# 1-TX510_KIT.net
KiCad netlist of a schematic drawn in Altium Designer
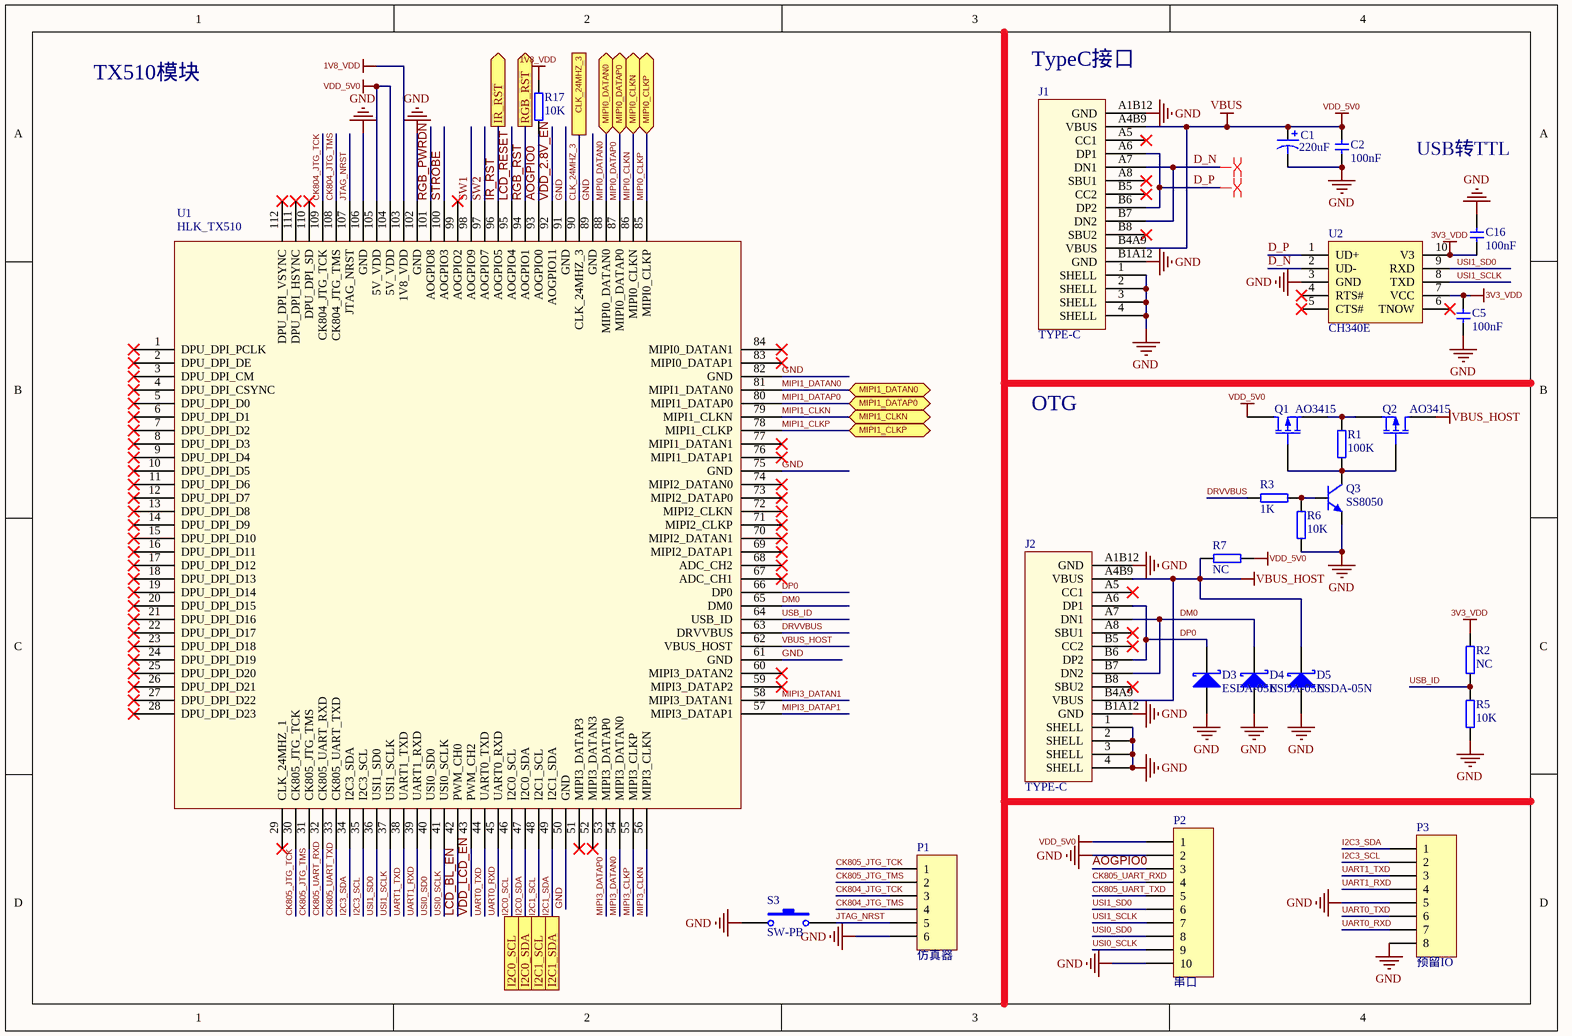
[diagram p0: 1-TX510_KIT.SchDoc]

(export (version "E")
  (design (tool "Eeschema 10.0.6"))
  (components
    (comp (ref "C1")
      (value "220uF")
      (footprint "SMD,6.3x7.7mm")
      (description "Polarized Capacitor (Radial)")
      (fields (field (name "Comment") "Cap Pol1") (field (name "PUBLISHER") "Altium Limited"))
      (libsource (lib "Miscellaneous Devices") (part "Cap Pol1"))
    )
    (comp (ref "C2")
      (value "100nF")
      (footprint "C0402")
      (description "C?")
      (libsource (lib "HNCY_SCH_Lib") (part "CAP1"))
    )
    (comp (ref "C5")
      (value "100nF")
      (footprint "C0402")
      (description "C?")
      (libsource (lib "HNCY_SCH_Lib") (part "CAP1"))
    )
    (comp (ref "C16")
      (value "100nF")
      (footprint "C0402")
      (description "C?")
      (libsource (lib "HNCY_SCH_Lib") (part "CAP1"))
    )
    (comp (ref "D3")
      (value "ESDA-05N")
      (footprint "R0402")
      (description "Silicon AF Schottky Diode for High-Speed Switching")
      (fields (field (name "PUBLISHER") "Altium Limited"))
      (libsource (lib "Miscellaneous Devices") (part "Diode BAS70"))
    )
    (comp (ref "D4")
      (value "ESDA-05N")
      (footprint "R0402")
      (description "Silicon AF Schottky Diode for High-Speed Switching")
      (fields (field (name "PUBLISHER") "Altium Limited"))
      (libsource (lib "Miscellaneous Devices") (part "Diode BAS70"))
    )
    (comp (ref "D5")
      (value "ESDA-05N")
      (footprint "R0402")
      (description "Silicon AF Schottky Diode for High-Speed Switching")
      (fields (field (name "PUBLISHER") "Altium Limited"))
      (libsource (lib "Miscellaneous Devices") (part "Diode BAS70"))
    )
    (comp (ref "J1") (value "TYPE-C") (footprint "TYPE-C16PIN") (libsource (lib "*") (part "TYPE-C16PIN")))
    (comp (ref "J2") (value "TYPE-C") (footprint "TYPE-C16PIN") (libsource (lib "*") (part "TYPE-C16PIN")))
    (comp (ref "P1")
      (value "仿真器")
      (footprint "HDR1X6")
      (description "Header, 6-Pin")
      (fields (field (name "PUBLISHER") "Altium Limited"))
      (libsource (lib "Miscellaneous Connectors") (part "Header 6"))
    )
    (comp (ref "P2")
      (value "串口")
      (footprint "HDR1X10")
      (description "Header, 10-Pin")
      (fields (field (name "PUBLISHER") "Altium Limited"))
      (libsource (lib "Miscellaneous Connectors") (part "Header 10"))
    )
    (comp (ref "P3")
      (value "预留IO")
      (footprint "HDR1X8")
      (description "Header, 8-Pin")
      (fields (field (name "PUBLISHER") "Altium Limited"))
      (libsource (lib "Miscellaneous Connectors") (part "Header 8"))
    )
    (comp (ref "Q1") (value "AO3415") (footprint "SOT-23") (libsource (lib "*") (part "AO3415")))
    (comp (ref "Q2") (value "AO3415") (footprint "SOT-23") (libsource (lib "*") (part "AO3415")))
    (comp (ref "Q3")
      (value "SS8050")
      (footprint "SOT23-BEC")
      (description "贴片三极管")
      (libsource (lib "HNCY_SCH_Lib") (part "NPN"))
    )
    (comp (ref "R1")
      (value "100K")
      (footprint "R0402")
      (description "R?")
      (libsource (lib "HNCY_SCH_Lib") (part "RES1"))
    )
    (comp (ref "R2")
      (value "NC")
      (footprint "R0402")
      (description "R?")
      (libsource (lib "HNCY_SCH_Lib") (part "RES1"))
    )
    (comp (ref "R3")
      (value "1K")
      (footprint "R0402")
      (description "R?")
      (libsource (lib "HNCY_SCH_Lib") (part "RES1"))
    )
    (comp (ref "R5")
      (value "10K")
      (footprint "R0402")
      (description "R?")
      (libsource (lib "HNCY_SCH_Lib") (part "RES1"))
    )
    (comp (ref "R6")
      (value "10K")
      (footprint "R0402")
      (description "R?")
      (libsource (lib "HNCY_SCH_Lib") (part "RES1"))
    )
    (comp (ref "R7")
      (value "NC")
      (footprint "RES_0603")
      (description "R?")
      (libsource (lib "HNCY_SCH_Lib") (part "RES1"))
    )
    (comp (ref "R17")
      (value "10K")
      (footprint "R0402")
      (description "R?")
      (libsource (lib "HNCY_SCH_Lib") (part "RES1"))
    )
    (comp (ref "S3")
      (value "SW-PB")
      (footprint "轻触开关4.5x4.5")
      (description "Switch")
      (fields (field (name "PUBLISHER") "Altium Limited"))
      (libsource (lib "Miscellaneous Devices") (part "SW-PB"))
    )
    (comp (ref "U1")
      (value "HLK_TX510")
      (footprint "HLK_TX510 _KIT")
      (libsource (lib "MY SCHLIB") (part "HLK_TX510"))
    )
    (comp (ref "U2") (value "CH340E") (footprint "MSOP-10") (libsource (lib "MY SCHLIB") (part "CH340E")))
  )
  (nets
    (net (code "1") (name "/AOGPIO0") (class "Default")
      (node (ref "P2") (pin "3") (pinfunction "3_3") (pintype "passive"))
      (node (ref "R17") (pin "1") (pinfunction "1_1") (pintype "passive"))
      (node (ref "U1") (pin "93") (pinfunction "AOGPIO0_93") (pintype "passive"))
    )
    (net (code "2") (name "/CK804_JTG_TCK") (class "Default")
      (node (ref "P1") (pin "3") (pinfunction "3_3") (pintype "passive"))
      (node (ref "U1") (pin "109") (pinfunction "CK804_JTG_TCK_109") (pintype "passive"))
    )
    (net (code "3") (name "/CK804_JTG_TMS") (class "Default")
      (node (ref "P1") (pin "4") (pinfunction "4_4") (pintype "passive"))
      (node (ref "U1") (pin "108") (pinfunction "CK804_JTG_TMS_108") (pintype "passive"))
    )
    (net (code "4") (name "/CK805_JTG_TCK") (class "Default")
      (node (ref "P1") (pin "1") (pinfunction "1_1") (pintype "passive"))
      (node (ref "U1") (pin "30") (pinfunction "CK805_JTG_TCK_30") (pintype "passive"))
    )
    (net (code "5") (name "/CK805_JTG_TMS") (class "Default")
      (node (ref "P1") (pin "2") (pinfunction "2_2") (pintype "passive"))
      (node (ref "U1") (pin "31") (pinfunction "CK805_JTG_TMS_31") (pintype "passive"))
    )
    (net (code "6") (name "/CK805_UART_RXD") (class "Default")
      (node (ref "P2") (pin "4") (pinfunction "4_4") (pintype "passive"))
      (node (ref "U1") (pin "32") (pinfunction "CK805_UART_RXD_32") (pintype "passive"))
    )
    (net (code "7") (name "/CK805_UART_TXD") (class "Default")
      (node (ref "P2") (pin "5") (pinfunction "5_5") (pintype "passive"))
      (node (ref "U1") (pin "33") (pinfunction "CK805_UART_TXD_33") (pintype "passive"))
    )
    (net (code "8") (name "/CLK_24MHZ_3") (class "Default")
      (node (ref "U1") (pin "90") (pinfunction "CLK_24MHZ_3_90") (pintype "passive"))
    )
    (net (code "9") (name "/DM0") (class "Default")
      (node (ref "D4") (pin "2") (pinfunction "K_2") (pintype "passive"))
      (node (ref "J2") (pin "A7") (pinfunction "DN1_A7") (pintype "passive"))
      (node (ref "J2") (pin "B7") (pinfunction "DN2_B7") (pintype "passive"))
      (node (ref "U1") (pin "65") (pinfunction "DM0_65") (pintype "passive"))
    )
    (net (code "10") (name "/DP0") (class "Default")
      (node (ref "D3") (pin "2") (pinfunction "K_2") (pintype "passive"))
      (node (ref "J2") (pin "A6") (pinfunction "DP1_A6") (pintype "passive"))
      (node (ref "J2") (pin "B6") (pinfunction "DP2_B6") (pintype "passive"))
      (node (ref "U1") (pin "66") (pinfunction "DP0_66") (pintype "passive"))
    )
    (net (code "11") (name "/DRVVBUS") (class "Default")
      (node (ref "R3") (pin "2") (pinfunction "2_2") (pintype "passive"))
      (node (ref "U1") (pin "63") (pinfunction "DRVVBUS_63") (pintype "passive"))
    )
    (net (code "12") (name "/D_N") (class "Default")
      (node (ref "J1") (pin "A7") (pinfunction "DN1_A7") (pintype "passive"))
      (node (ref "J1") (pin "B7") (pinfunction "DN2_B7") (pintype "passive"))
      (node (ref "U2") (pin "2") (pinfunction "UD-_2") (pintype "passive"))
    )
    (net (code "13") (name "/D_P") (class "Default")
      (node (ref "J1") (pin "A6") (pinfunction "DP1_A6") (pintype "passive"))
      (node (ref "J1") (pin "B6") (pinfunction "DP2_B6") (pintype "passive"))
      (node (ref "U2") (pin "1") (pinfunction "UD+_1") (pintype "passive"))
    )
    (net (code "14") (name "/I2C0_SCL") (class "Default")
      (node (ref "U1") (pin "46") (pinfunction "I2C0_SCL_46") (pintype "passive"))
    )
    (net (code "15") (name "/I2C0_SDA") (class "Default")
      (node (ref "U1") (pin "47") (pinfunction "I2C0_SDA_47") (pintype "passive"))
    )
    (net (code "16") (name "/I2C1_SCL") (class "Default")
      (node (ref "U1") (pin "48") (pinfunction "I2C1_SCL_48") (pintype "passive"))
    )
    (net (code "17") (name "/I2C1_SDA") (class "Default")
      (node (ref "U1") (pin "49") (pinfunction "I2C1_SDA_49") (pintype "passive"))
    )
    (net (code "18") (name "/I2C3_SCL") (class "Default")
      (node (ref "P3") (pin "2") (pinfunction "2_2") (pintype "passive"))
      (node (ref "U1") (pin "35") (pinfunction "I2C3_SCL_35") (pintype "passive"))
    )
    (net (code "19") (name "/I2C3_SDA") (class "Default")
      (node (ref "P3") (pin "1") (pinfunction "1_1") (pintype "passive"))
      (node (ref "U1") (pin "34") (pinfunction "I2C3_SDA_34") (pintype "passive"))
    )
    (net (code "20") (name "/IR_RST") (class "Default")
      (node (ref "U1") (pin "96") (pinfunction "AOGPIO5_96") (pintype "passive"))
    )
    (net (code "21") (name "/JTAG_NRST") (class "Default")
      (node (ref "P1") (pin "5") (pinfunction "5_5") (pintype "passive"))
      (node (ref "S3") (pin "2") (pinfunction "2_2") (pintype "passive"))
      (node (ref "U1") (pin "107") (pinfunction "JTAG_NRST_107") (pintype "passive"))
    )
    (net (code "22") (name "/LCD_BL_EN") (class "Default")
      (node (ref "U1") (pin "42") (pinfunction "PWM_CH0_42") (pintype "passive"))
    )
    (net (code "23") (name "/LCD_RESET") (class "Default")
      (node (ref "U1") (pin "95") (pinfunction "AOGPIO4_95") (pintype "passive"))
    )
    (net (code "24") (name "/MIPI0_CLKN") (class "Default")
      (node (ref "U1") (pin "86") (pinfunction "MIPI0_CLKN_86") (pintype "passive"))
    )
    (net (code "25") (name "/MIPI0_CLKP") (class "Default")
      (node (ref "U1") (pin "85") (pinfunction "MIPI0_CLKP_85") (pintype "passive"))
    )
    (net (code "26") (name "/MIPI0_DATAN0") (class "Default")
      (node (ref "U1") (pin "88") (pinfunction "MIPI0_DATAN0_88") (pintype "passive"))
    )
    (net (code "27") (name "/MIPI0_DATAP0") (class "Default")
      (node (ref "U1") (pin "87") (pinfunction "MIPI0_DATAP0_87") (pintype "passive"))
    )
    (net (code "28") (name "/MIPI1_CLKN") (class "Default")
      (node (ref "U1") (pin "79") (pinfunction "MIPI1_CLKN_79") (pintype "passive"))
    )
    (net (code "29") (name "/MIPI1_CLKP") (class "Default")
      (node (ref "U1") (pin "78") (pinfunction "MIPI1_CLKP_78") (pintype "passive"))
    )
    (net (code "30") (name "/MIPI1_DATAN0") (class "Default")
      (node (ref "U1") (pin "81") (pinfunction "MIPI1_DATAN0_81") (pintype "passive"))
    )
    (net (code "31") (name "/MIPI1_DATAP0") (class "Default")
      (node (ref "U1") (pin "80") (pinfunction "MIPI1_DATAP0_80") (pintype "passive"))
    )
    (net (code "32") (name "/MIPI3_CLKN") (class "Default")
      (node (ref "U1") (pin "56") (pinfunction "MIPI3_CLKN_56") (pintype "passive"))
    )
    (net (code "33") (name "/MIPI3_CLKP") (class "Default")
      (node (ref "U1") (pin "55") (pinfunction "MIPI3_CLKP_55") (pintype "passive"))
    )
    (net (code "34") (name "/MIPI3_DATAN0") (class "Default")
      (node (ref "U1") (pin "54") (pinfunction "MIPI3_DATAN0_54") (pintype "passive"))
    )
    (net (code "35") (name "/MIPI3_DATAN1") (class "Default")
      (node (ref "U1") (pin "58") (pinfunction "MIPI3_DATAN1_58") (pintype "passive"))
    )
    (net (code "36") (name "/MIPI3_DATAP0") (class "Default")
      (node (ref "U1") (pin "53") (pinfunction "MIPI3_DATAP0_53") (pintype "passive"))
    )
    (net (code "37") (name "/MIPI3_DATAP1") (class "Default")
      (node (ref "U1") (pin "57") (pinfunction "MIPI3_DATAP1_57") (pintype "passive"))
    )
    (net (code "38") (name "/RGB_PWRDN") (class "Default")
      (node (ref "U1") (pin "101") (pinfunction "AOGPIO8_101") (pintype "passive"))
    )
    (net (code "39") (name "/RGB_RST") (class "Default")
      (node (ref "U1") (pin "94") (pinfunction "AOGPIO1_94") (pintype "passive"))
    )
    (net (code "40") (name "/STROBE") (class "Default")
      (node (ref "U1") (pin "100") (pinfunction "AOGPIO3_100") (pintype "passive"))
    )
    (net (code "41") (name "/SW1") (class "Default")
      (node (ref "U1") (pin "98") (pinfunction "AOGPIO9_98") (pintype "passive"))
    )
    (net (code "42") (name "/SW2") (class "Default")
      (node (ref "U1") (pin "97") (pinfunction "AOGPIO7_97") (pintype "passive"))
    )
    (net (code "43") (name "/UART0_RXD") (class "Default")
      (node (ref "P3") (pin "7") (pinfunction "7_7") (pintype "passive"))
      (node (ref "U1") (pin "45") (pinfunction "UART0_RXD_45") (pintype "passive"))
    )
    (net (code "44") (name "/UART0_TXD") (class "Default")
      (node (ref "P3") (pin "6") (pinfunction "6_6") (pintype "passive"))
      (node (ref "U1") (pin "44") (pinfunction "UART0_TXD_44") (pintype "passive"))
    )
    (net (code "45") (name "/UART1_RXD") (class "Default")
      (node (ref "P3") (pin "4") (pinfunction "4_4") (pintype "passive"))
      (node (ref "U1") (pin "39") (pinfunction "UART1_RXD_39") (pintype "passive"))
    )
    (net (code "46") (name "/UART1_TXD") (class "Default")
      (node (ref "P3") (pin "3") (pinfunction "3_3") (pintype "passive"))
      (node (ref "U1") (pin "38") (pinfunction "UART1_TXD_38") (pintype "passive"))
    )
    (net (code "47") (name "/USB_ID") (class "Default")
      (node (ref "R2") (pin "1") (pinfunction "1_1") (pintype "passive"))
      (node (ref "R5") (pin "2") (pinfunction "2_2") (pintype "passive"))
      (node (ref "U1") (pin "64") (pinfunction "USB_ID_64") (pintype "passive"))
    )
    (net (code "48") (name "/USI0_SCLK") (class "Default")
      (node (ref "P2") (pin "9") (pinfunction "9_9") (pintype "passive"))
      (node (ref "U1") (pin "41") (pinfunction "USI0_SCLK_41") (pintype "passive"))
    )
    (net (code "49") (name "/USI0_SD0") (class "Default")
      (node (ref "P2") (pin "8") (pinfunction "8_8") (pintype "passive"))
      (node (ref "U1") (pin "40") (pinfunction "USI0_SD0_40") (pintype "passive"))
    )
    (net (code "50") (name "/USI1_SCLK") (class "Default")
      (node (ref "P2") (pin "7") (pinfunction "7_7") (pintype "passive"))
      (node (ref "U1") (pin "37") (pinfunction "USI1_SCLK_37") (pintype "passive"))
      (node (ref "U2") (pin "8") (pinfunction "TXD_8") (pintype "passive"))
    )
    (net (code "51") (name "/USI1_SD0") (class "Default")
      (node (ref "P2") (pin "6") (pinfunction "6_6") (pintype "passive"))
      (node (ref "U1") (pin "36") (pinfunction "USI1_SD0_36") (pintype "passive"))
      (node (ref "U2") (pin "9") (pinfunction "RXD_9") (pintype "passive"))
    )
    (net (code "52") (name "/VDD_2.8V_EN") (class "Default")
      (node (ref "U1") (pin "92") (pinfunction "AOGPIO11_92") (pintype "passive"))
    )
    (net (code "53") (name "/VDD_LCD_EN") (class "Default")
      (node (ref "U1") (pin "43") (pinfunction "PWM_CH2_43") (pintype "passive"))
    )
    (net (code "54") (name "1V8_VDD") (class "Default")
      (node (ref "R17") (pin "2") (pinfunction "2_2") (pintype "passive"))
      (node (ref "U1") (pin "103") (pinfunction "1V8_VDD_103") (pintype "passive"))
    )
    (net (code "55") (name "3V3_VDD") (class "Default")
      (node (ref "C16") (pin "1") (pintype "passive"))
      (node (ref "C5") (pin "2") (pintype "passive"))
      (node (ref "R2") (pin "2") (pinfunction "2_2") (pintype "passive"))
      (node (ref "U2") (pin "10") (pinfunction "V3_10") (pintype "passive"))
      (node (ref "U2") (pin "7") (pinfunction "VCC_7") (pintype "passive"))
    )
    (net (code "56") (name "GND") (class "Default")
      (node (ref "C1") (pin "2") (pinfunction "2_2") (pintype "passive"))
      (node (ref "C16") (pin "2") (pintype "passive"))
      (node (ref "C2") (pin "1") (pintype "passive"))
      (node (ref "C5") (pin "1") (pintype "passive"))
      (node (ref "D3") (pin "1") (pinfunction "A_1") (pintype "passive"))
      (node (ref "D4") (pin "1") (pinfunction "A_1") (pintype "passive"))
      (node (ref "D5") (pin "1") (pinfunction "A_1") (pintype "passive"))
      (node (ref "J1") (pin "1") (pinfunction "SHELL_1") (pintype "passive"))
      (node (ref "J1") (pin "2") (pinfunction "SHELL_2") (pintype "passive"))
      (node (ref "J1") (pin "3") (pinfunction "SHELL_3") (pintype "passive"))
      (node (ref "J1") (pin "4") (pinfunction "SHELL_4") (pintype "passive"))
      (node (ref "J1") (pin "A1B12") (pinfunction "GND_A1B12") (pintype "passive"))
      (node (ref "J1") (pin "B1A12") (pinfunction "GND_B1A12") (pintype "passive"))
      (node (ref "J2") (pin "1") (pinfunction "SHELL_1") (pintype "passive"))
      (node (ref "J2") (pin "2") (pinfunction "SHELL_2") (pintype "passive"))
      (node (ref "J2") (pin "3") (pinfunction "SHELL_3") (pintype "passive"))
      (node (ref "J2") (pin "4") (pinfunction "SHELL_4") (pintype "passive"))
      (node (ref "J2") (pin "A1B12") (pinfunction "GND_A1B12") (pintype "passive"))
      (node (ref "J2") (pin "B1A12") (pinfunction "GND_B1A12") (pintype "passive"))
      (node (ref "P1") (pin "6") (pinfunction "6_6") (pintype "passive"))
      (node (ref "P2") (pin "10") (pinfunction "10_10") (pintype "passive"))
      (node (ref "P2") (pin "2") (pinfunction "2_2") (pintype "passive"))
      (node (ref "P3") (pin "5") (pinfunction "5_5") (pintype "passive"))
      (node (ref "P3") (pin "8") (pinfunction "8_8") (pintype "passive"))
      (node (ref "Q3") (pin "E") (pinfunction "E_E") (pintype "passive"))
      (node (ref "R5") (pin "1") (pinfunction "1_1") (pintype "passive"))
      (node (ref "R6") (pin "1") (pinfunction "1_1") (pintype "passive"))
      (node (ref "S3") (pin "1") (pinfunction "1_1") (pintype "passive"))
      (node (ref "U1") (pin "102") (pinfunction "GND_102") (pintype "passive"))
      (node (ref "U1") (pin "106") (pinfunction "GND_106") (pintype "passive"))
      (node (ref "U1") (pin "50") (pinfunction "GND_50") (pintype "passive"))
      (node (ref "U1") (pin "61") (pinfunction "GND_61") (pintype "passive"))
      (node (ref "U1") (pin "75") (pinfunction "GND_75") (pintype "passive"))
      (node (ref "U1") (pin "82") (pinfunction "GND_82") (pintype "passive"))
      (node (ref "U1") (pin "89") (pinfunction "GND_89") (pintype "passive"))
      (node (ref "U1") (pin "91") (pinfunction "GND_91") (pintype "passive"))
      (node (ref "U2") (pin "3") (pinfunction "GND_3") (pintype "passive"))
    )
    (net (code "57") (name "Net-(Q1-G)") (class "Default")
      (node (ref "Q1") (pin "1") (pinfunction "G_1") (pintype "passive"))
      (node (ref "Q2") (pin "1") (pinfunction "G_1") (pintype "passive"))
      (node (ref "Q3") (pin "C") (pinfunction "C_C") (pintype "passive"))
      (node (ref "R1") (pin "1") (pinfunction "1_1") (pintype "passive"))
    )
    (net (code "58") (name "Net-(Q1-S)") (class "Default")
      (node (ref "Q1") (pin "2") (pinfunction "S_2") (pintype "passive"))
      (node (ref "Q2") (pin "2") (pinfunction "S_2") (pintype "passive"))
      (node (ref "R1") (pin "2") (pinfunction "2_2") (pintype "passive"))
    )
    (net (code "59") (name "Net-(Q3-PadB)") (class "Default")
      (node (ref "Q3") (pin "B") (pinfunction "B_B") (pintype "passive"))
      (node (ref "R3") (pin "1") (pinfunction "1_1") (pintype "passive"))
      (node (ref "R6") (pin "2") (pinfunction "2_2") (pintype "passive"))
    )
    (net (code "60") (name "VBUS") (class "Default")
      (node (ref "C1") (pin "1") (pinfunction "1_1") (pintype "passive"))
      (node (ref "C2") (pin "2") (pintype "passive"))
      (node (ref "J1") (pin "A4B9") (pinfunction "VBUS_A4B9") (pintype "passive"))
      (node (ref "J1") (pin "B4A9") (pinfunction "VBUS_B4A9") (pintype "passive"))
      (node (ref "P2") (pin "1") (pinfunction "1_1") (pintype "passive"))
      (node (ref "Q1") (pin "3") (pinfunction "D_3") (pintype "passive"))
      (node (ref "R7") (pin "1") (pinfunction "1_1") (pintype "passive"))
      (node (ref "U1") (pin "104") (pinfunction "5V_VDD_104") (pintype "passive"))
      (node (ref "U1") (pin "105") (pinfunction "5V_VDD_105") (pintype "passive"))
    )
    (net (code "61") (name "VBUS_HOST") (class "Default")
      (node (ref "D5") (pin "2") (pinfunction "K_2") (pintype "passive"))
      (node (ref "J2") (pin "A4B9") (pinfunction "VBUS_A4B9") (pintype "passive"))
      (node (ref "J2") (pin "B4A9") (pinfunction "VBUS_B4A9") (pintype "passive"))
      (node (ref "Q2") (pin "3") (pinfunction "D_3") (pintype "passive"))
      (node (ref "R7") (pin "2") (pinfunction "2_2") (pintype "passive"))
      (node (ref "U1") (pin "62") (pinfunction "VBUS_HOST_62") (pintype "passive"))
    )
    (net (code "62") (name "unconnected-(J1-CC1-PadA5)") (class "Default")
      (node (ref "J1") (pin "A5") (pinfunction "CC1_A5") (pintype "passive+no_connect"))
    )
    (net (code "63") (name "unconnected-(J1-CC2-PadB5)") (class "Default")
      (node (ref "J1") (pin "B5") (pinfunction "CC2_B5") (pintype "passive+no_connect"))
    )
    (net (code "64") (name "unconnected-(J1-SBU1-PadA8)") (class "Default")
      (node (ref "J1") (pin "A8") (pinfunction "SBU1_A8") (pintype "passive+no_connect"))
    )
    (net (code "65") (name "unconnected-(J1-SBU2-PadB8)") (class "Default")
      (node (ref "J1") (pin "B8") (pinfunction "SBU2_B8") (pintype "passive+no_connect"))
    )
    (net (code "66") (name "unconnected-(J2-CC1-PadA5)") (class "Default")
      (node (ref "J2") (pin "A5") (pinfunction "CC1_A5") (pintype "passive+no_connect"))
    )
    (net (code "67") (name "unconnected-(J2-CC2-PadB5)") (class "Default")
      (node (ref "J2") (pin "B5") (pinfunction "CC2_B5") (pintype "passive+no_connect"))
    )
    (net (code "68") (name "unconnected-(J2-SBU1-PadA8)") (class "Default")
      (node (ref "J2") (pin "A8") (pinfunction "SBU1_A8") (pintype "passive+no_connect"))
    )
    (net (code "69") (name "unconnected-(J2-SBU2-PadB8)") (class "Default")
      (node (ref "J2") (pin "B8") (pinfunction "SBU2_B8") (pintype "passive+no_connect"))
    )
    (net (code "70") (name "unconnected-(U1-ADC_CH1-Pad67)") (class "Default")
      (node (ref "U1") (pin "67") (pinfunction "ADC_CH1_67") (pintype "passive+no_connect"))
    )
    (net (code "71") (name "unconnected-(U1-ADC_CH2-Pad68)") (class "Default")
      (node (ref "U1") (pin "68") (pinfunction "ADC_CH2_68") (pintype "passive+no_connect"))
    )
    (net (code "72") (name "unconnected-(U1-AOGPIO2-Pad99)") (class "Default")
      (node (ref "U1") (pin "99") (pinfunction "AOGPIO2_99") (pintype "passive+no_connect"))
    )
    (net (code "73") (name "unconnected-(U1-CLK_24MHZ_1-Pad29)") (class "Default")
      (node (ref "U1") (pin "29") (pinfunction "CLK_24MHZ_1_29") (pintype "passive+no_connect"))
    )
    (net (code "74") (name "unconnected-(U1-DPU_DPI_CM-Pad3)") (class "Default")
      (node (ref "U1") (pin "3") (pinfunction "DPU_DPI_CM_3") (pintype "passive+no_connect"))
    )
    (net (code "75") (name "unconnected-(U1-DPU_DPI_CSYNC-Pad4)") (class "Default")
      (node (ref "U1") (pin "4") (pinfunction "DPU_DPI_CSYNC_4") (pintype "passive+no_connect"))
    )
    (net (code "76") (name "unconnected-(U1-DPU_DPI_D0-Pad5)") (class "Default")
      (node (ref "U1") (pin "5") (pinfunction "DPU_DPI_D0_5") (pintype "passive+no_connect"))
    )
    (net (code "77") (name "unconnected-(U1-DPU_DPI_D1-Pad6)") (class "Default")
      (node (ref "U1") (pin "6") (pinfunction "DPU_DPI_D1_6") (pintype "passive+no_connect"))
    )
    (net (code "78") (name "unconnected-(U1-DPU_DPI_D2-Pad7)") (class "Default")
      (node (ref "U1") (pin "7") (pinfunction "DPU_DPI_D2_7") (pintype "passive+no_connect"))
    )
    (net (code "79") (name "unconnected-(U1-DPU_DPI_D3-Pad8)") (class "Default")
      (node (ref "U1") (pin "8") (pinfunction "DPU_DPI_D3_8") (pintype "passive+no_connect"))
    )
    (net (code "80") (name "unconnected-(U1-DPU_DPI_D4-Pad9)") (class "Default")
      (node (ref "U1") (pin "9") (pinfunction "DPU_DPI_D4_9") (pintype "passive+no_connect"))
    )
    (net (code "81") (name "unconnected-(U1-DPU_DPI_D5-Pad10)") (class "Default")
      (node (ref "U1") (pin "10") (pinfunction "DPU_DPI_D5_10") (pintype "passive+no_connect"))
    )
    (net (code "82") (name "unconnected-(U1-DPU_DPI_D6-Pad11)") (class "Default")
      (node (ref "U1") (pin "11") (pinfunction "DPU_DPI_D6_11") (pintype "passive+no_connect"))
    )
    (net (code "83") (name "unconnected-(U1-DPU_DPI_D7-Pad12)") (class "Default")
      (node (ref "U1") (pin "12") (pinfunction "DPU_DPI_D7_12") (pintype "passive+no_connect"))
    )
    (net (code "84") (name "unconnected-(U1-DPU_DPI_D8-Pad13)") (class "Default")
      (node (ref "U1") (pin "13") (pinfunction "DPU_DPI_D8_13") (pintype "passive+no_connect"))
    )
    (net (code "85") (name "unconnected-(U1-DPU_DPI_D9-Pad14)") (class "Default")
      (node (ref "U1") (pin "14") (pinfunction "DPU_DPI_D9_14") (pintype "passive+no_connect"))
    )
    (net (code "86") (name "unconnected-(U1-DPU_DPI_D10-Pad15)") (class "Default")
      (node (ref "U1") (pin "15") (pinfunction "DPU_DPI_D10_15") (pintype "passive+no_connect"))
    )
    (net (code "87") (name "unconnected-(U1-DPU_DPI_D11-Pad16)") (class "Default")
      (node (ref "U1") (pin "16") (pinfunction "DPU_DPI_D11_16") (pintype "passive+no_connect"))
    )
    (net (code "88") (name "unconnected-(U1-DPU_DPI_D12-Pad17)") (class "Default")
      (node (ref "U1") (pin "17") (pinfunction "DPU_DPI_D12_17") (pintype "passive+no_connect"))
    )
    (net (code "89") (name "unconnected-(U1-DPU_DPI_D13-Pad18)") (class "Default")
      (node (ref "U1") (pin "18") (pinfunction "DPU_DPI_D13_18") (pintype "passive+no_connect"))
    )
    (net (code "90") (name "unconnected-(U1-DPU_DPI_D14-Pad19)") (class "Default")
      (node (ref "U1") (pin "19") (pinfunction "DPU_DPI_D14_19") (pintype "passive+no_connect"))
    )
    (net (code "91") (name "unconnected-(U1-DPU_DPI_D15-Pad20)") (class "Default")
      (node (ref "U1") (pin "20") (pinfunction "DPU_DPI_D15_20") (pintype "passive+no_connect"))
    )
    (net (code "92") (name "unconnected-(U1-DPU_DPI_D16-Pad21)") (class "Default")
      (node (ref "U1") (pin "21") (pinfunction "DPU_DPI_D16_21") (pintype "passive+no_connect"))
    )
    (net (code "93") (name "unconnected-(U1-DPU_DPI_D17-Pad22)") (class "Default")
      (node (ref "U1") (pin "22") (pinfunction "DPU_DPI_D17_22") (pintype "passive+no_connect"))
    )
    (net (code "94") (name "unconnected-(U1-DPU_DPI_D18-Pad23)") (class "Default")
      (node (ref "U1") (pin "23") (pinfunction "DPU_DPI_D18_23") (pintype "passive+no_connect"))
    )
    (net (code "95") (name "unconnected-(U1-DPU_DPI_D19-Pad24)") (class "Default")
      (node (ref "U1") (pin "24") (pinfunction "DPU_DPI_D19_24") (pintype "passive+no_connect"))
    )
    (net (code "96") (name "unconnected-(U1-DPU_DPI_D20-Pad25)") (class "Default")
      (node (ref "U1") (pin "25") (pinfunction "DPU_DPI_D20_25") (pintype "passive+no_connect"))
    )
    (net (code "97") (name "unconnected-(U1-DPU_DPI_D21-Pad26)") (class "Default")
      (node (ref "U1") (pin "26") (pinfunction "DPU_DPI_D21_26") (pintype "passive+no_connect"))
    )
    (net (code "98") (name "unconnected-(U1-DPU_DPI_D22-Pad27)") (class "Default")
      (node (ref "U1") (pin "27") (pinfunction "DPU_DPI_D22_27") (pintype "passive+no_connect"))
    )
    (net (code "99") (name "unconnected-(U1-DPU_DPI_D23-Pad28)") (class "Default")
      (node (ref "U1") (pin "28") (pinfunction "DPU_DPI_D23_28") (pintype "passive+no_connect"))
    )
    (net (code "100") (name "unconnected-(U1-DPU_DPI_DE-Pad2)") (class "Default")
      (node (ref "U1") (pin "2") (pinfunction "DPU_DPI_DE_2") (pintype "passive+no_connect"))
    )
    (net (code "101") (name "unconnected-(U1-DPU_DPI_HSYNC-Pad111)") (class "Default")
      (node (ref "U1") (pin "111") (pinfunction "DPU_DPI_HSYNC_111") (pintype "passive+no_connect"))
    )
    (net (code "102") (name "unconnected-(U1-DPU_DPI_PCLK-Pad1)") (class "Default")
      (node (ref "U1") (pin "1") (pinfunction "DPU_DPI_PCLK_1") (pintype "passive+no_connect"))
    )
    (net (code "103") (name "unconnected-(U1-DPU_DPI_SD-Pad110)") (class "Default")
      (node (ref "U1") (pin "110") (pinfunction "DPU_DPI_SD_110") (pintype "passive+no_connect"))
    )
    (net (code "104") (name "unconnected-(U1-DPU_DPI_VSYNC-Pad112)") (class "Default")
      (node (ref "U1") (pin "112") (pinfunction "DPU_DPI_VSYNC_112") (pintype "passive+no_connect"))
    )
    (net (code "105") (name "unconnected-(U1-MIPI0_DATAN1-Pad84)") (class "Default")
      (node (ref "U1") (pin "84") (pinfunction "MIPI0_DATAN1_84") (pintype "passive+no_connect"))
    )
    (net (code "106") (name "unconnected-(U1-MIPI0_DATAP1-Pad83)") (class "Default")
      (node (ref "U1") (pin "83") (pinfunction "MIPI0_DATAP1_83") (pintype "passive+no_connect"))
    )
    (net (code "107") (name "unconnected-(U1-MIPI1_DATAN1-Pad77)") (class "Default")
      (node (ref "U1") (pin "77") (pinfunction "MIPI1_DATAN1_77") (pintype "passive+no_connect"))
    )
    (net (code "108") (name "unconnected-(U1-MIPI1_DATAP1-Pad76)") (class "Default")
      (node (ref "U1") (pin "76") (pinfunction "MIPI1_DATAP1_76") (pintype "passive+no_connect"))
    )
    (net (code "109") (name "unconnected-(U1-MIPI2_CLKN-Pad72)") (class "Default")
      (node (ref "U1") (pin "72") (pinfunction "MIPI2_CLKN_72") (pintype "passive+no_connect"))
    )
    (net (code "110") (name "unconnected-(U1-MIPI2_CLKP-Pad71)") (class "Default")
      (node (ref "U1") (pin "71") (pinfunction "MIPI2_CLKP_71") (pintype "passive+no_connect"))
    )
    (net (code "111") (name "unconnected-(U1-MIPI2_DATAN0-Pad74)") (class "Default")
      (node (ref "U1") (pin "74") (pinfunction "MIPI2_DATAN0_74") (pintype "passive+no_connect"))
    )
    (net (code "112") (name "unconnected-(U1-MIPI2_DATAN1-Pad70)") (class "Default")
      (node (ref "U1") (pin "70") (pinfunction "MIPI2_DATAN1_70") (pintype "passive+no_connect"))
    )
    (net (code "113") (name "unconnected-(U1-MIPI2_DATAP0-Pad73)") (class "Default")
      (node (ref "U1") (pin "73") (pinfunction "MIPI2_DATAP0_73") (pintype "passive+no_connect"))
    )
    (net (code "114") (name "unconnected-(U1-MIPI2_DATAP1-Pad69)") (class "Default")
      (node (ref "U1") (pin "69") (pinfunction "MIPI2_DATAP1_69") (pintype "passive+no_connect"))
    )
    (net (code "115") (name "unconnected-(U1-MIPI3_DATAN2-Pad60)") (class "Default")
      (node (ref "U1") (pin "60") (pinfunction "MIPI3_DATAN2_60") (pintype "passive+no_connect"))
    )
    (net (code "116") (name "unconnected-(U1-MIPI3_DATAN3-Pad52)") (class "Default")
      (node (ref "U1") (pin "52") (pinfunction "MIPI3_DATAN3_52") (pintype "passive+no_connect"))
    )
    (net (code "117") (name "unconnected-(U1-MIPI3_DATAP2-Pad59)") (class "Default")
      (node (ref "U1") (pin "59") (pinfunction "MIPI3_DATAP2_59") (pintype "passive+no_connect"))
    )
    (net (code "118") (name "unconnected-(U1-MIPI3_DATAP3-Pad51)") (class "Default")
      (node (ref "U1") (pin "51") (pinfunction "MIPI3_DATAP3_51") (pintype "passive+no_connect"))
    )
    (net (code "119") (name "unconnected-(U2-CTS#-Pad5)") (class "Default")
      (node (ref "U2") (pin "5") (pinfunction "CTS#_5") (pintype "passive+no_connect"))
    )
    (net (code "120") (name "unconnected-(U2-RTS#-Pad4)") (class "Default")
      (node (ref "U2") (pin "4") (pinfunction "RTS#_4") (pintype "passive+no_connect"))
    )
    (net (code "121") (name "unconnected-(U2-TNOW-Pad6)") (class "Default")
      (node (ref "U2") (pin "6") (pinfunction "TNOW_6") (pintype "passive+no_connect"))
    )
  )
)
